# AMU-S27-V00-MX120G-Interface.net
KiCad netlist of a schematic drawn in Altium Designer
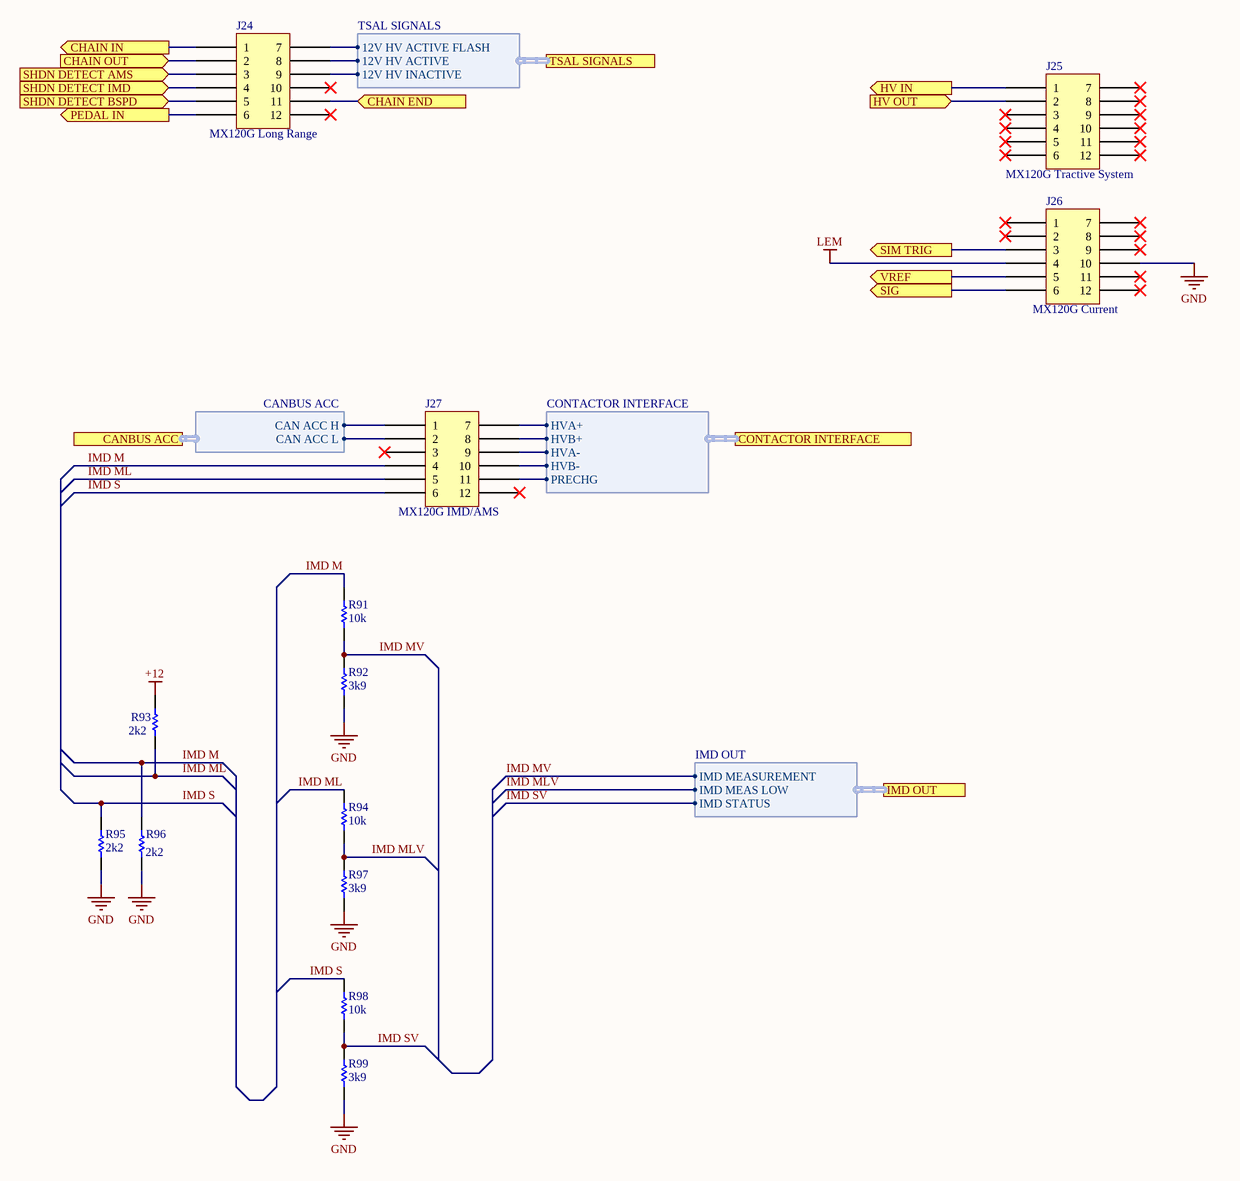
[diagram p0: AMU-S27-V00-MX120G-Interface.SchDoc]

(export (version "E")
  (design (tool "Eeschema 10.0.6"))
  (components
    (comp (ref "J24")
      (value "MX120G Long Range")
      (footprint "MX120G")
      (description "MX120G with standard connector layout")
      (libsource (lib "QUTMS_MolexLibrary") (part "MX120G"))
    )
    (comp (ref "J25")
      (value "MX120G Tractive System")
      (footprint "MX120G")
      (description "MX120G with standard connector layout")
      (libsource (lib "QUTMS_MolexLibrary") (part "MX120G"))
    )
    (comp (ref "J26")
      (value "MX120G Current")
      (footprint "MX120G")
      (description "MX120G with standard connector layout")
      (libsource (lib "QUTMS_MolexLibrary") (part "MX120G"))
    )
    (comp (ref "J27")
      (value "MX120G IMD/AMS")
      (footprint "MX120G")
      (description "MX120G with standard connector layout")
      (libsource (lib "QUTMS_MolexLibrary") (part "MX120G"))
    )
    (comp (ref "R91")
      (value "10k")
      (footprint "Res_ThinFilm_0603")
      (description "Resistor, SMD, 10k, 0.1W, 1%, 0603")
      (libsource (lib "StandardResistors") (part "10k 1% 0603"))
    )
    (comp (ref "R92")
      (value "3k9")
      (footprint "Res_ThinFilm_0603")
      (description "Resistor, SMD, 3k9, 0.1W, 5%, 0603")
      (libsource (lib "StandardResistors") (part "3k9 5% 0603"))
    )
    (comp (ref "R93")
      (value "2k2")
      (footprint "Res_ThinFilm_0603")
      (description "Resistor, SMD, 2k2, 0.1W, 5%, 0603")
      (libsource (lib "StandardResistors") (part "2k2 5% 0603"))
    )
    (comp (ref "R94")
      (value "10k")
      (footprint "Res_ThinFilm_0603")
      (description "Resistor, SMD, 10k, 0.1W, 1%, 0603")
      (libsource (lib "StandardResistors") (part "10k 1% 0603"))
    )
    (comp (ref "R95")
      (value "2k2")
      (footprint "Res_ThinFilm_0603")
      (description "Resistor, SMD, 2k2, 0.1W, 5%, 0603")
      (libsource (lib "StandardResistors") (part "2k2 5% 0603"))
    )
    (comp (ref "R96")
      (value "2k2")
      (footprint "Res_ThinFilm_0603")
      (description "Resistor, SMD, 2k2, 0.1W, 5%, 0603")
      (libsource (lib "StandardResistors") (part "2k2 5% 0603"))
    )
    (comp (ref "R97")
      (value "3k9")
      (footprint "Res_ThinFilm_0603")
      (description "Resistor, SMD, 3k9, 0.1W, 5%, 0603")
      (libsource (lib "StandardResistors") (part "3k9 5% 0603"))
    )
    (comp (ref "R98")
      (value "10k")
      (footprint "Res_ThinFilm_0603")
      (description "Resistor, SMD, 10k, 0.1W, 1%, 0603")
      (libsource (lib "StandardResistors") (part "10k 1% 0603"))
    )
    (comp (ref "R99")
      (value "3k9")
      (footprint "Res_ThinFilm_0603")
      (description "Resistor, SMD, 3k9, 0.1W, 5%, 0603")
      (libsource (lib "StandardResistors") (part "3k9 5% 0603"))
    )
  )
  (nets
    (net (code "9") (name "+12") (class "Default")
      (node (ref "R93") (pin "2") (pinfunction "2_2") (pintype "passive"))
    )
    (net (code "10") (name "/12V HV ACTIVE") (class "Default")
      (node (ref "J24") (pin "8") (pinfunction "8_8") (pintype "passive"))
    )
    (net (code "11") (name "/12V HV ACTIVE FLASH") (class "Default")
      (node (ref "J24") (pin "7") (pinfunction "7_7") (pintype "passive"))
    )
    (net (code "12") (name "/12V HV INACTIVE") (class "Default")
      (node (ref "J24") (pin "9") (pinfunction "9_9") (pintype "passive"))
    )
    (net (code "13") (name "/CAN ACC H") (class "Default")
      (node (ref "J27") (pin "1") (pinfunction "1_1") (pintype "passive"))
    )
    (net (code "14") (name "/CAN ACC L") (class "Default")
      (node (ref "J27") (pin "2") (pinfunction "2_2") (pintype "passive"))
    )
    (net (code "15") (name "/CHAIN END") (class "Default")
      (node (ref "J24") (pin "11") (pinfunction "11_11") (pintype "passive"))
    )
    (net (code "16") (name "/CHAIN IN") (class "Default")
      (node (ref "J24") (pin "1") (pinfunction "1_1") (pintype "passive"))
    )
    (net (code "17") (name "/CHAIN OUT") (class "Default")
      (node (ref "J24") (pin "2") (pinfunction "2_2") (pintype "passive"))
    )
    (net (code "18") (name "/HV IN") (class "Default")
      (node (ref "J25") (pin "1") (pinfunction "1_1") (pintype "passive"))
    )
    (net (code "19") (name "/HV OUT") (class "Default")
      (node (ref "J25") (pin "2") (pinfunction "2_2") (pintype "passive"))
    )
    (net (code "20") (name "/HVA+") (class "Default")
      (node (ref "J27") (pin "7") (pinfunction "7_7") (pintype "passive"))
    )
    (net (code "21") (name "/HVA-") (class "Default")
      (node (ref "J27") (pin "9") (pinfunction "9_9") (pintype "passive"))
    )
    (net (code "22") (name "/HVB+") (class "Default")
      (node (ref "J27") (pin "8") (pinfunction "8_8") (pintype "passive"))
    )
    (net (code "23") (name "/HVB-") (class "Default")
      (node (ref "J27") (pin "10") (pinfunction "10_10") (pintype "passive"))
    )
    (net (code "24") (name "/IMD M") (class "Default")
      (node (ref "J27") (pin "4") (pinfunction "4_4") (pintype "passive"))
      (node (ref "R91") (pin "2") (pinfunction "2_2") (pintype "passive"))
      (node (ref "R96") (pin "2") (pinfunction "2_2") (pintype "passive"))
    )
    (net (code "25") (name "/IMD ML") (class "Default")
      (node (ref "J27") (pin "5") (pinfunction "5_5") (pintype "passive"))
      (node (ref "R93") (pin "1") (pinfunction "1_1") (pintype "passive"))
      (node (ref "R94") (pin "2") (pinfunction "2_2") (pintype "passive"))
    )
    (net (code "26") (name "/IMD MLV") (class "Default")
      (node (ref "R94") (pin "1") (pinfunction "1_1") (pintype "passive"))
      (node (ref "R97") (pin "2") (pinfunction "2_2") (pintype "passive"))
    )
    (net (code "27") (name "/IMD MV") (class "Default")
      (node (ref "R91") (pin "1") (pinfunction "1_1") (pintype "passive"))
      (node (ref "R92") (pin "2") (pinfunction "2_2") (pintype "passive"))
    )
    (net (code "28") (name "/IMD S") (class "Default")
      (node (ref "J27") (pin "6") (pinfunction "6_6") (pintype "passive"))
      (node (ref "R95") (pin "2") (pinfunction "2_2") (pintype "passive"))
      (node (ref "R98") (pin "2") (pinfunction "2_2") (pintype "passive"))
    )
    (net (code "29") (name "/IMD SV") (class "Default")
      (node (ref "R98") (pin "1") (pinfunction "1_1") (pintype "passive"))
      (node (ref "R99") (pin "2") (pinfunction "2_2") (pintype "passive"))
    )
    (net (code "30") (name "/PEDAL IN") (class "Default")
      (node (ref "J24") (pin "6") (pinfunction "6_6") (pintype "passive"))
    )
    (net (code "31") (name "/PRECHG") (class "Default")
      (node (ref "J27") (pin "11") (pinfunction "11_11") (pintype "passive"))
    )
    (net (code "32") (name "/SHDN DETECT AMS") (class "Default")
      (node (ref "J24") (pin "3") (pinfunction "3_3") (pintype "passive"))
    )
    (net (code "33") (name "/SHDN DETECT BSPD") (class "Default")
      (node (ref "J24") (pin "5") (pinfunction "5_5") (pintype "passive"))
    )
    (net (code "34") (name "/SHDN DETECT IMD") (class "Default")
      (node (ref "J24") (pin "4") (pinfunction "4_4") (pintype "passive"))
    )
    (net (code "35") (name "/SIG") (class "Default")
      (node (ref "J26") (pin "6") (pinfunction "6_6") (pintype "passive"))
    )
    (net (code "36") (name "/SIM TRIG") (class "Default")
      (node (ref "J26") (pin "3") (pinfunction "3_3") (pintype "passive"))
    )
    (net (code "37") (name "/VREF") (class "Default")
      (node (ref "J26") (pin "5") (pinfunction "5_5") (pintype "passive"))
    )
    (net (code "42") (name "GND") (class "Default")
      (node (ref "J26") (pin "10") (pinfunction "10_10") (pintype "passive"))
      (node (ref "R92") (pin "1") (pinfunction "1_1") (pintype "passive"))
      (node (ref "R95") (pin "1") (pinfunction "1_1") (pintype "passive"))
      (node (ref "R96") (pin "1") (pinfunction "1_1") (pintype "passive"))
      (node (ref "R97") (pin "1") (pinfunction "1_1") (pintype "passive"))
      (node (ref "R99") (pin "1") (pinfunction "1_1") (pintype "passive"))
    )
    (net (code "43") (name "LEM") (class "Default")
      (node (ref "J26") (pin "4") (pinfunction "4_4") (pintype "passive"))
    )
    (net (code "44") (name "unconnected-(J24-Pad10)") (class "Default")
      (node (ref "J24") (pin "10") (pinfunction "10_10") (pintype "passive+no_connect"))
    )
    (net (code "45") (name "unconnected-(J24-Pad12)") (class "Default")
      (node (ref "J24") (pin "12") (pinfunction "12_12") (pintype "passive+no_connect"))
    )
    (net (code "46") (name "unconnected-(J25-Pad3)") (class "Default")
      (node (ref "J25") (pin "3") (pinfunction "3_3") (pintype "passive+no_connect"))
    )
    (net (code "47") (name "unconnected-(J25-Pad4)") (class "Default")
      (node (ref "J25") (pin "4") (pinfunction "4_4") (pintype "passive+no_connect"))
    )
    (net (code "48") (name "unconnected-(J25-Pad5)") (class "Default")
      (node (ref "J25") (pin "5") (pinfunction "5_5") (pintype "passive+no_connect"))
    )
    (net (code "49") (name "unconnected-(J25-Pad6)") (class "Default")
      (node (ref "J25") (pin "6") (pinfunction "6_6") (pintype "passive+no_connect"))
    )
    (net (code "50") (name "unconnected-(J25-Pad7)") (class "Default")
      (node (ref "J25") (pin "7") (pinfunction "7_7") (pintype "passive+no_connect"))
    )
    (net (code "51") (name "unconnected-(J25-Pad8)") (class "Default")
      (node (ref "J25") (pin "8") (pinfunction "8_8") (pintype "passive+no_connect"))
    )
    (net (code "52") (name "unconnected-(J25-Pad9)") (class "Default")
      (node (ref "J25") (pin "9") (pinfunction "9_9") (pintype "passive+no_connect"))
    )
    (net (code "53") (name "unconnected-(J25-Pad10)") (class "Default")
      (node (ref "J25") (pin "10") (pinfunction "10_10") (pintype "passive+no_connect"))
    )
    (net (code "54") (name "unconnected-(J25-Pad11)") (class "Default")
      (node (ref "J25") (pin "11") (pinfunction "11_11") (pintype "passive+no_connect"))
    )
    (net (code "55") (name "unconnected-(J25-Pad12)") (class "Default")
      (node (ref "J25") (pin "12") (pinfunction "12_12") (pintype "passive+no_connect"))
    )
    (net (code "56") (name "unconnected-(J26-Pad1)") (class "Default")
      (node (ref "J26") (pin "1") (pinfunction "1_1") (pintype "passive+no_connect"))
    )
    (net (code "57") (name "unconnected-(J26-Pad2)") (class "Default")
      (node (ref "J26") (pin "2") (pinfunction "2_2") (pintype "passive+no_connect"))
    )
    (net (code "58") (name "unconnected-(J26-Pad7)") (class "Default")
      (node (ref "J26") (pin "7") (pinfunction "7_7") (pintype "passive+no_connect"))
    )
    (net (code "59") (name "unconnected-(J26-Pad8)") (class "Default")
      (node (ref "J26") (pin "8") (pinfunction "8_8") (pintype "passive+no_connect"))
    )
    (net (code "60") (name "unconnected-(J26-Pad9)") (class "Default")
      (node (ref "J26") (pin "9") (pinfunction "9_9") (pintype "passive+no_connect"))
    )
    (net (code "61") (name "unconnected-(J26-Pad11)") (class "Default")
      (node (ref "J26") (pin "11") (pinfunction "11_11") (pintype "passive+no_connect"))
    )
    (net (code "62") (name "unconnected-(J26-Pad12)") (class "Default")
      (node (ref "J26") (pin "12") (pinfunction "12_12") (pintype "passive+no_connect"))
    )
    (net (code "63") (name "unconnected-(J27-Pad3)") (class "Default")
      (node (ref "J27") (pin "3") (pinfunction "3_3") (pintype "passive+no_connect"))
    )
    (net (code "64") (name "unconnected-(J27-Pad12)") (class "Default")
      (node (ref "J27") (pin "12") (pinfunction "12_12") (pintype "passive+no_connect"))
    )
  )
)
